# Capacitores.net
KiCad netlist of a schematic drawn in Altium Designer
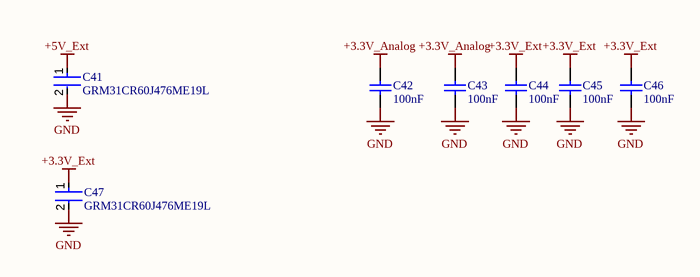
[diagram p0: Capacitores.SchDoc]

(export (version "E")
  (design (tool "Eeschema 10.0.6"))
  (components
    (comp (ref "C41")
      (value "GRM31CR60J476ME19L")
      (footprint "FP-GRM31C-0_2-e0_3_0_8-IPC_C")
      (description "Chip Multilayer Ceramic Capacitors for General Purpose, 1206, 47uF, X5R, 15%, 20%, 6.3V")
      (fields (field (name "TOLERANCE") "20%") (field (name "VOLTAGE") "6.3V"))
      (libsource (lib "Altium Content Vault") (part "02cd4be3c70576c341d710602a673aa"))
    )
    (comp (ref "C42")
      (value "100nF")
      (footprint "CAPC0603(1608)100_L")
      (description "Multilayer Ceramic Capacitor, 0.1 uF, 16 V, ± 20%, X7R, 0603 [1608 Metric]")
      (fields (field (name "TOLERANCE") "20%") (field (name "Comment") "VJ0603Y104MXJCW1BC"))
      (libsource (lib "UFCG - Universidade Federal de Campina Grande") (part "CAP"))
    )
    (comp (ref "C43")
      (value "100nF")
      (footprint "CAPC0603(1608)100_L")
      (description "Multilayer Ceramic Capacitor, 0.1 uF, 16 V, ± 20%, X7R, 0603 [1608 Metric]")
      (fields (field (name "TOLERANCE") "20%") (field (name "Comment") "VJ0603Y104MXJCW1BC"))
      (libsource (lib "UFCG - Universidade Federal de Campina Grande") (part "CAP"))
    )
    (comp (ref "C44")
      (value "100nF")
      (footprint "CAPC0603(1608)100_L")
      (description "Multilayer Ceramic Capacitor, 0.1 uF, 16 V, ± 20%, X7R, 0603 [1608 Metric]")
      (fields (field (name "TOLERANCE") "20%") (field (name "Comment") "VJ0603Y104MXJCW1BC"))
      (libsource (lib "UFCG - Universidade Federal de Campina Grande") (part "CAP"))
    )
    (comp (ref "C45")
      (value "100nF")
      (footprint "CAPC0603(1608)100_L")
      (description "Multilayer Ceramic Capacitor, 0.1 uF, 16 V, ± 20%, X7R, 0603 [1608 Metric]")
      (fields (field (name "TOLERANCE") "20%") (field (name "Comment") "VJ0603Y104MXJCW1BC"))
      (libsource (lib "UFCG - Universidade Federal de Campina Grande") (part "CAP"))
    )
    (comp (ref "C46")
      (value "100nF")
      (footprint "CAPC0603(1608)100_L")
      (description "Multilayer Ceramic Capacitor, 0.1 uF, 16 V, ± 20%, X7R, 0603 [1608 Metric]")
      (fields (field (name "TOLERANCE") "20%") (field (name "Comment") "VJ0603Y104MXJCW1BC"))
      (libsource (lib "UFCG - Universidade Federal de Campina Grande") (part "CAP"))
    )
    (comp (ref "C47")
      (value "GRM31CR60J476ME19L")
      (footprint "FP-GRM31C-0_2-e0_3_0_8-IPC_C")
      (description "Chip Multilayer Ceramic Capacitors for General Purpose, 1206, 47uF, X5R, 15%, 20%, 6.3V")
      (fields (field (name "TOLERANCE") "20%") (field (name "VOLTAGE") "6.3V"))
      (libsource (lib "Altium Content Vault") (part "02cd4be3c70576c341d710602a673aa"))
    )
  )
  (nets
    (net (code "1") (name "+3.3V_Analog") (class "Default")
      (node (ref "C42") (pin "1") (pinfunction "1_1") (pintype "passive"))
      (node (ref "C43") (pin "1") (pinfunction "1_1") (pintype "passive"))
    )
    (net (code "2") (name "+3.3V_Ext") (class "Default")
      (node (ref "C44") (pin "2") (pinfunction "2_2") (pintype "passive"))
      (node (ref "C45") (pin "2") (pinfunction "2_2") (pintype "passive"))
      (node (ref "C46") (pin "2") (pinfunction "2_2") (pintype "passive"))
      (node (ref "C47") (pin "1") (pinfunction "1_1") (pintype "passive"))
    )
    (net (code "3") (name "+5V_Ext") (class "Default")
      (node (ref "C41") (pin "1") (pinfunction "1_1") (pintype "passive"))
    )
    (net (code "4") (name "GND") (class "Default")
      (node (ref "C41") (pin "2") (pinfunction "2_2") (pintype "passive"))
      (node (ref "C42") (pin "2") (pinfunction "2_2") (pintype "passive"))
      (node (ref "C43") (pin "2") (pinfunction "2_2") (pintype "passive"))
      (node (ref "C44") (pin "1") (pinfunction "1_1") (pintype "passive"))
      (node (ref "C45") (pin "1") (pinfunction "1_1") (pintype "passive"))
      (node (ref "C46") (pin "1") (pinfunction "1_1") (pintype "passive"))
      (node (ref "C47") (pin "2") (pinfunction "2_2") (pintype "passive"))
    )
  )
)
